# PBC.net
KiCad netlist of a schematic drawn in Altium Designer
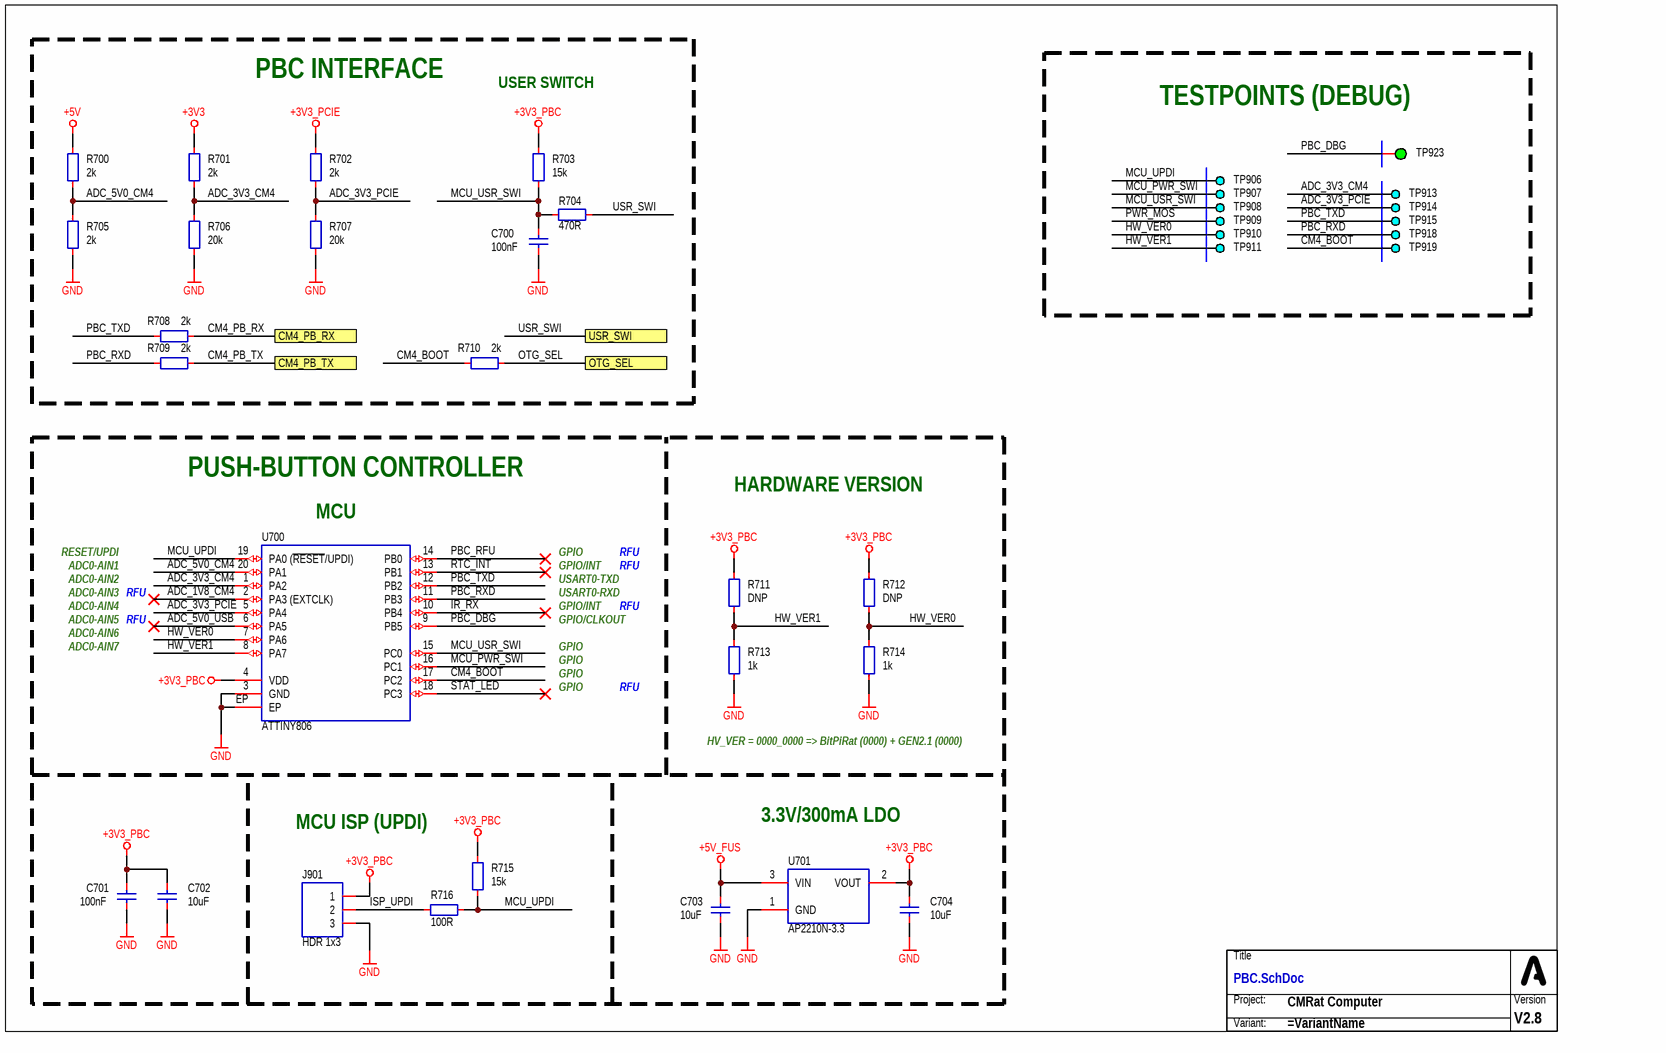
[diagram p0: PBC.SchDoc]

(export (version "E")
  (design (tool "Eeschema 10.0.6"))
  (components
    (comp (ref "C700")
      (value "100nF")
      (footprint "CAP_0603_R")
      (description "Capacitor; MLCC; 100nF; 10V X5R")
      (fields (field (name "MANUFACTURER") "YAGEO") (field (name "MPN") "CC0603KRX7R9BB104"))
      (libsource (lib "MirFol_db_local") (part "CAP"))
    )
    (comp (ref "C701")
      (value "100nF")
      (footprint "CAP_0603_R")
      (description "Capacitor; MLCC; 100nF; 10V X5R")
      (fields (field (name "MANUFACTURER") "YAGEO") (field (name "MPN") "CC0603KRX7R9BB104"))
      (libsource (lib "MirFol_db_local") (part "CAP"))
    )
    (comp (ref "C702")
      (value "10uF")
      (footprint "CAP_0603_R")
      (description "CAP SMD 10u/10V ±10% 10V X5R (0603)")
      (fields
        (field (name "MANUFACTURER") "Samsung Electro-Mechanics")
        (field (name "MPN") "CL10A106KP8NNNC")
      )
      (libsource (lib "MirFol_db_local") (part "CAP"))
    )
    (comp (ref "C703")
      (value "10uF")
      (footprint "CAP_0603_R")
      (description "CAP SMD 10u/10V ±10% 10V X5R (0603)")
      (fields
        (field (name "MANUFACTURER") "Samsung Electro-Mechanics")
        (field (name "MPN") "CL10A106KP8NNNC")
      )
      (libsource (lib "MirFol_db_local") (part "CAP"))
    )
    (comp (ref "C704")
      (value "10uF")
      (footprint "CAP_0603_R")
      (description "CAP SMD 10u/10V ±10% 10V X5R (0603)")
      (fields
        (field (name "MANUFACTURER") "Samsung Electro-Mechanics")
        (field (name "MPN") "CL10A106KP8NNNC")
      )
      (libsource (lib "MirFol_db_local") (part "CAP"))
    )
    (comp (ref "J901")
      (value "HDR 1x3")
      (footprint "CON_HDR_P254_1X03_STR")
      (description "CONN THT / HEADER / PITCH 2,54mm / VERTICAL / (3 PIN)")
      (fields
        (field (name "MANUFACTURER") "Ckmtw(Shenzhen Cankemeng)")
        (field (name "MPN") "B-2100S03P-A110")
      )
      (libsource (lib "MirFol_lib") (part "CON_1X03_COL"))
    )
    (comp (ref "R700")
      (value "2k")
      (footprint "RES_0603_R")
      (description "Resistor; Thick Film; 2k2; 1%; 100mW; 100PPM; 75V; Standard; SMD; 0603 (1608);")
      (fields (field (name "MANUFACTURER") "UNI-ROYAL(Uniroyal Elec)") (field (name "MPN") "0603WAF2001T5E"))
      (libsource (lib "") (part "RES_1"))
    )
    (comp (ref "R701")
      (value "2k")
      (footprint "RES_0603_R")
      (description "Resistor; Thick Film; 2k2; 1%; 100mW; 100PPM; 75V; Standard; SMD; 0603 (1608);")
      (fields (field (name "MANUFACTURER") "UNI-ROYAL(Uniroyal Elec)") (field (name "MPN") "0603WAF2001T5E"))
      (libsource (lib "") (part "RES_1"))
    )
    (comp (ref "R702")
      (value "2k")
      (footprint "RES_0603_R")
      (description "Resistor; Thick Film; 2k2; 1%; 100mW; 100PPM; 75V; Standard; SMD; 0603 (1608);")
      (fields (field (name "MANUFACTURER") "UNI-ROYAL(Uniroyal Elec)") (field (name "MPN") "0603WAF2001T5E"))
      (libsource (lib "") (part "RES_1"))
    )
    (comp (ref "R703")
      (value "15k")
      (footprint "RES_0603_R")
      (description "Resistor; Thick Film; 15k; 1%; 100mW; 100PPM; 75V; Standard; SMD; 0603 (1608);")
      (fields (field (name "MANUFACTURER") "UNI-ROYAL(Uniroyal Elec)") (field (name "MPN") "0603WAF1502T5E"))
      (libsource (lib "") (part "RES_2"))
    )
    (comp (ref "R704")
      (value "470R")
      (footprint "RES_0603_R")
      (description "Resistor; Thick Film; 470R; 1%; 100mW; 100PPM; 75V; Standard; SMD; 0603 (1608);")
      (fields (field (name "MANUFACTURER") "UNI-ROYAL(Uniroyal Elec)") (field (name "MPN") "0603WAF4700T5E"))
      (libsource (lib "") (part "RES_3"))
    )
    (comp (ref "R705")
      (value "2k")
      (footprint "RES_0603_R")
      (description "Resistor; Thick Film; 2k2; 1%; 100mW; 100PPM; 75V; Standard; SMD; 0603 (1608);")
      (fields (field (name "MANUFACTURER") "UNI-ROYAL(Uniroyal Elec)") (field (name "MPN") "0603WAF2001T5E"))
      (libsource (lib "") (part "RES_1"))
    )
    (comp (ref "R706")
      (value "20k")
      (footprint "RES_0603_R")
      (description "Resistor; Thick Film; 20k; SMD; 0603 (1608);")
      (fields (field (name "MANUFACTURER") "UNI-ROYAL(Uniroyal Elec)") (field (name "MPN") "0603WAF2002T5E"))
      (libsource (lib "") (part "RES_2"))
    )
    (comp (ref "R707")
      (value "20k")
      (footprint "RES_0603_R")
      (description "Resistor; Thick Film; 20k; SMD; 0603 (1608);")
      (fields (field (name "MANUFACTURER") "UNI-ROYAL(Uniroyal Elec)") (field (name "MPN") "0603WAF2002T5E"))
      (libsource (lib "") (part "RES_2"))
    )
    (comp (ref "R708")
      (value "2k")
      (footprint "RES_0603_R")
      (description "Resistor; Thick Film; 2k2; 1%; 100mW; 100PPM; 75V; Standard; SMD; 0603 (1608);")
      (fields (field (name "MANUFACTURER") "UNI-ROYAL(Uniroyal Elec)") (field (name "MPN") "0603WAF2001T5E"))
      (libsource (lib "MirFol_db_local") (part "RES"))
    )
    (comp (ref "R709")
      (value "2k")
      (footprint "RES_0603_R")
      (description "Resistor; Thick Film; 2k2; 1%; 100mW; 100PPM; 75V; Standard; SMD; 0603 (1608);")
      (fields (field (name "MANUFACTURER") "UNI-ROYAL(Uniroyal Elec)") (field (name "MPN") "0603WAF2001T5E"))
      (libsource (lib "MirFol_db_local") (part "RES"))
    )
    (comp (ref "R710")
      (value "2k")
      (footprint "RES_0603_R")
      (description "Resistor; Thick Film; 2k2; 1%; 100mW; 100PPM; 75V; Standard; SMD; 0603 (1608);")
      (fields (field (name "MANUFACTURER") "UNI-ROYAL(Uniroyal Elec)") (field (name "MPN") "0603WAF2001T5E"))
      (libsource (lib "") (part "RES_3"))
    )
    (comp (ref "R711") (value "DNP") (footprint "RES_0603_R") (libsource (lib "") (part "RES_2")))
    (comp (ref "R712") (value "DNP") (footprint "RES_0603_R") (libsource (lib "") (part "RES_2")))
    (comp (ref "R713")
      (value "1k")
      (footprint "RES_0603_R")
      (description "Resistor; Thick Film; 1k; 1%; 100mW; 100PPM; 75V; Standard; SMD; 0603 (1608);")
      (fields (field (name "MANUFACTURER") "UNI-ROYAL(Uniroyal Elec)") (field (name "MPN") "0603WAF1001T5E"))
      (libsource (lib "") (part "RES_2"))
    )
    (comp (ref "R714")
      (value "1k")
      (footprint "RES_0603_R")
      (description "Resistor; Thick Film; 1k; 1%; 100mW; 100PPM; 75V; Standard; SMD; 0603 (1608);")
      (fields (field (name "MANUFACTURER") "UNI-ROYAL(Uniroyal Elec)") (field (name "MPN") "0603WAF1001T5E"))
      (libsource (lib "") (part "RES_2"))
    )
    (comp (ref "R715")
      (value "15k")
      (footprint "RES_0603_R")
      (description "Resistor; Thick Film; 15k; 1%; 100mW; 100PPM; 75V; Standard; SMD; 0603 (1608);")
      (fields (field (name "MANUFACTURER") "UNI-ROYAL(Uniroyal Elec)") (field (name "MPN") "0603WAF1502T5E"))
      (libsource (lib "") (part "RES_2"))
    )
    (comp (ref "R716")
      (value "100R")
      (footprint "RES_0603_R")
      (description "Resistor; Thick Film; 100R; 1%; 100mW; 100PPM; 75V; Standard; SMD; 0603 (1608);")
      (fields (field (name "MANUFACTURER") "UNI-ROYAL(Uniroyal Elec)") (field (name "MPN") "0603WAF1000T5E"))
      (libsource (lib "MirFol_db_local") (part "RES"))
    )
    (comp (ref "TB700") (value "~") (libsource (lib "Symbols_NO_BOM") (part "SCH_TITLE_BLOCK_SIMPLE_NODATE")))
    (comp (ref "TP906")
      (value "DEBUG")
      (footprint "PCB_TP_DBG_50")
      (description "PCB Marking; Test Point (Debug);")
      (libsource (lib "MirFol_lib") (part "PCB_TP_DBG"))
    )
    (comp (ref "TP907")
      (value "DEBUG")
      (footprint "PCB_TP_DBG_50")
      (description "PCB Marking; Test Point (Debug);")
      (libsource (lib "MirFol_lib") (part "PCB_TP_DBG"))
    )
    (comp (ref "TP908")
      (value "DEBUG")
      (footprint "PCB_TP_DBG_50")
      (description "PCB Marking; Test Point (Debug);")
      (libsource (lib "MirFol_lib") (part "PCB_TP_DBG"))
    )
    (comp (ref "TP909")
      (value "DEBUG")
      (footprint "PCB_TP_DBG_50")
      (description "PCB Marking; Test Point (Debug);")
      (libsource (lib "MirFol_lib") (part "PCB_TP_DBG"))
    )
    (comp (ref "TP910")
      (value "DEBUG")
      (footprint "PCB_TP_DBG_50")
      (description "PCB Marking; Test Point (Debug);")
      (libsource (lib "MirFol_lib") (part "PCB_TP_DBG"))
    )
    (comp (ref "TP911")
      (value "DEBUG")
      (footprint "PCB_TP_DBG_50")
      (description "PCB Marking; Test Point (Debug);")
      (libsource (lib "MirFol_lib") (part "PCB_TP_DBG"))
    )
    (comp (ref "TP913")
      (value "DEBUG")
      (footprint "PCB_TP_DBG_50")
      (description "PCB Marking; Test Point (Debug);")
      (libsource (lib "MirFol_lib") (part "PCB_TP_DBG"))
    )
    (comp (ref "TP914")
      (value "DEBUG")
      (footprint "PCB_TP_DBG_50")
      (description "PCB Marking; Test Point (Debug);")
      (libsource (lib "MirFol_lib") (part "PCB_TP_DBG"))
    )
    (comp (ref "TP915")
      (value "DEBUG")
      (footprint "PCB_TP_DBG_50")
      (description "PCB Marking; Test Point (Debug);")
      (libsource (lib "MirFol_lib") (part "PCB_TP_DBG"))
    )
    (comp (ref "TP918")
      (value "DEBUG")
      (footprint "PCB_TP_DBG_50")
      (description "PCB Marking; Test Point (Debug);")
      (libsource (lib "MirFol_lib") (part "PCB_TP_DBG"))
    )
    (comp (ref "TP919")
      (value "DEBUG")
      (footprint "PCB_TP_DBG_50")
      (description "PCB Marking; Test Point (Debug);")
      (libsource (lib "MirFol_lib") (part "PCB_TP_DBG"))
    )
    (comp (ref "TP923")
      (value "ICT")
      (footprint "PCB_TP_ICT_100")
      (description "Test Point (ICT)")
      (libsource (lib "MirFol_lib") (part "PCB_TP_ICT"))
    )
    (comp (ref "U700")
      (value "ATTINY806")
      (footprint "ICC_QFN20_300X300X90_P40_EP_R")
      (description "IC; MCU; tinyAVR 8-bit MCU, 20MHz, 8kB flash, 512B RAM, USART, SPI, TWI, VQFN package")
      (fields
        (field (name "MANUFACTURER") "Microchip Technology (Atmel)")
        (field (name "MPN") "ATTINY806-MNR")
      )
      (libsource (lib "Pineberry_Lib") (part "ICC_MCP_ATTINY406_806_1606_VQFN20"))
    )
    (comp (ref "U701")
      (value "AP2210N-3.3")
      (footprint "PKG_SOT23-3L_SC59_P190_R")
      (fields (field (name "MANUFACTURER") "Diodes Incorporated") (field (name "MPN") "AP2210N-3.3TRG1"))
      (libsource (lib "Pineberry_Lib") (part "ICC_DIO_AP2210N-3.3TR"))
    )
  )
  (nets
    (net (code "1") (name "+3V3") (class "Default")
      (node (ref "R701") (pin "1") (pinfunction "1_1") (pintype "passive"))
    )
    (net (code "2") (name "+3V3_PBC") (class "Default")
      (node (ref "C701") (pin "2") (pintype "passive"))
      (node (ref "C702") (pin "2") (pintype "passive"))
      (node (ref "C704") (pin "2") (pintype "passive"))
      (node (ref "J901") (pin "1") (pinfunction "1_1") (pintype "passive"))
      (node (ref "R703") (pin "2") (pinfunction "2_2") (pintype "passive"))
      (node (ref "R711") (pin "2") (pinfunction "2_2") (pintype "passive"))
      (node (ref "R712") (pin "2") (pinfunction "2_2") (pintype "passive"))
      (node (ref "R715") (pin "2") (pinfunction "2_2") (pintype "passive"))
      (node (ref "U700") (pin "4") (pinfunction "VDD_4") (pintype "power_in"))
      (node (ref "U701") (pin "2") (pinfunction "VOUT_2") (pintype "power_in"))
    )
    (net (code "3") (name "+3V3_PCIE") (class "Default")
      (node (ref "R702") (pin "1") (pinfunction "1_1") (pintype "passive"))
    )
    (net (code "4") (name "+5V") (class "Default")
      (node (ref "R700") (pin "1") (pinfunction "1_1") (pintype "passive"))
    )
    (net (code "5") (name "+5V_FUS") (class "Default")
      (node (ref "C703") (pin "2") (pintype "passive"))
      (node (ref "U701") (pin "3") (pinfunction "VIN_3") (pintype "power_in"))
    )
    (net (code "6") (name "/ADC_1V8_CM4") (class "Default")
      (node (ref "U700") (pin "2") (pinfunction "PA3_(EXTCLK)_2") (pintype "bidirectional+no_connect"))
    )
    (net (code "7") (name "/ADC_3V3_CM4") (class "Default")
      (node (ref "R701") (pin "2") (pinfunction "2_2") (pintype "passive"))
      (node (ref "R706") (pin "2") (pinfunction "2_2") (pintype "passive"))
      (node (ref "TP913") (pin "1") (pinfunction "1_1") (pintype "passive"))
      (node (ref "U700") (pin "1") (pinfunction "PA2_1") (pintype "bidirectional"))
    )
    (net (code "8") (name "/ADC_3V3_PCIE") (class "Default")
      (node (ref "R702") (pin "2") (pinfunction "2_2") (pintype "passive"))
      (node (ref "R707") (pin "2") (pinfunction "2_2") (pintype "passive"))
      (node (ref "TP914") (pin "1") (pinfunction "1_1") (pintype "passive"))
      (node (ref "U700") (pin "5") (pinfunction "PA4_5") (pintype "bidirectional"))
    )
    (net (code "9") (name "/ADC_5V0_CM4") (class "Default")
      (node (ref "R700") (pin "2") (pinfunction "2_2") (pintype "passive"))
      (node (ref "R705") (pin "1") (pinfunction "1_1") (pintype "passive"))
      (node (ref "U700") (pin "20") (pinfunction "PA1_20") (pintype "bidirectional"))
    )
    (net (code "10") (name "/ADC_5V0_USB") (class "Default")
      (node (ref "U700") (pin "6") (pinfunction "PA5_6") (pintype "bidirectional+no_connect"))
    )
    (net (code "11") (name "/CM4_BOOT") (class "Default")
      (node (ref "R710") (pin "2") (pinfunction "2_2") (pintype "passive"))
      (node (ref "TP919") (pin "1") (pinfunction "1_1") (pintype "passive"))
      (node (ref "U700") (pin "17") (pinfunction "PC2_17") (pintype "bidirectional"))
    )
    (net (code "12") (name "/CM4_PB_RX") (class "Default")
      (node (ref "R708") (pin "2") (pinfunction "2_2") (pintype "passive"))
    )
    (net (code "13") (name "/CM4_PB_TX") (class "Default")
      (node (ref "R709") (pin "2") (pinfunction "2_2") (pintype "passive"))
    )
    (net (code "14") (name "/HW_VER0") (class "Default")
      (node (ref "R712") (pin "1") (pinfunction "1_1") (pintype "passive"))
      (node (ref "R714") (pin "2") (pinfunction "2_2") (pintype "passive"))
      (node (ref "TP910") (pin "1") (pinfunction "1_1") (pintype "passive"))
      (node (ref "U700") (pin "7") (pinfunction "PA6_7") (pintype "bidirectional"))
    )
    (net (code "15") (name "/HW_VER1") (class "Default")
      (node (ref "R711") (pin "1") (pinfunction "1_1") (pintype "passive"))
      (node (ref "R713") (pin "2") (pinfunction "2_2") (pintype "passive"))
      (node (ref "TP911") (pin "1") (pinfunction "1_1") (pintype "passive"))
      (node (ref "U700") (pin "8") (pinfunction "PA7_8") (pintype "bidirectional"))
    )
    (net (code "16") (name "/IR_RX") (class "Default")
      (node (ref "U700") (pin "10") (pinfunction "PB4_10") (pintype "bidirectional+no_connect"))
    )
    (net (code "17") (name "/ISP_UPDI") (class "Default")
      (node (ref "J901") (pin "2") (pinfunction "2_2") (pintype "passive"))
      (node (ref "R716") (pin "1") (pinfunction "1_1") (pintype "passive"))
    )
    (net (code "18") (name "/MCU_PWR_SWI") (class "Default")
      (node (ref "TP907") (pin "1") (pinfunction "1_1") (pintype "passive"))
      (node (ref "U700") (pin "16") (pinfunction "PC1_16") (pintype "bidirectional"))
    )
    (net (code "19") (name "/MCU_UPDI") (class "Default")
      (node (ref "R715") (pin "1") (pinfunction "1_1") (pintype "passive"))
      (node (ref "R716") (pin "2") (pinfunction "2_2") (pintype "passive"))
      (node (ref "TP906") (pin "1") (pinfunction "1_1") (pintype "passive"))
      (node (ref "U700") (pin "19") (pinfunction "PA0_(~{RESET}/UPDI)_19") (pintype "bidirectional"))
    )
    (net (code "20") (name "/MCU_USR_SWI") (class "Default")
      (node (ref "C700") (pin "2") (pintype "passive"))
      (node (ref "R703") (pin "1") (pinfunction "1_1") (pintype "passive"))
      (node (ref "R704") (pin "2") (pinfunction "2_2") (pintype "passive"))
      (node (ref "TP908") (pin "1") (pinfunction "1_1") (pintype "passive"))
      (node (ref "U700") (pin "15") (pinfunction "PC0_15") (pintype "bidirectional"))
    )
    (net (code "21") (name "/OTG_SEL") (class "Default")
      (node (ref "R710") (pin "1") (pinfunction "1_1") (pintype "passive"))
    )
    (net (code "22") (name "/PBC_DBG") (class "Default")
      (node (ref "TP923") (pin "1") (pinfunction "1_1") (pintype "passive"))
      (node (ref "U700") (pin "9") (pinfunction "PB5_9") (pintype "bidirectional"))
    )
    (net (code "23") (name "/PBC_RFU") (class "Default")
      (node (ref "U700") (pin "14") (pinfunction "PB0_14") (pintype "bidirectional+no_connect"))
    )
    (net (code "24") (name "/PBC_RXD") (class "Default")
      (node (ref "R709") (pin "1") (pinfunction "1_1") (pintype "passive"))
      (node (ref "TP918") (pin "1") (pinfunction "1_1") (pintype "passive"))
      (node (ref "U700") (pin "11") (pinfunction "PB3_11") (pintype "bidirectional"))
    )
    (net (code "25") (name "/PBC_TXD") (class "Default")
      (node (ref "R708") (pin "1") (pinfunction "1_1") (pintype "passive"))
      (node (ref "TP915") (pin "1") (pinfunction "1_1") (pintype "passive"))
      (node (ref "U700") (pin "12") (pinfunction "PB2_12") (pintype "bidirectional"))
    )
    (net (code "26") (name "/PWR_MOS") (class "Default")
      (node (ref "TP909") (pin "1") (pinfunction "1_1") (pintype "passive"))
    )
    (net (code "27") (name "/RTC_INT") (class "Default")
      (node (ref "U700") (pin "13") (pinfunction "PB1_13") (pintype "bidirectional+no_connect"))
    )
    (net (code "28") (name "/STAT_LED") (class "Default")
      (node (ref "U700") (pin "18") (pinfunction "PC3_18") (pintype "bidirectional+no_connect"))
    )
    (net (code "29") (name "/USR_SWI") (class "Default")
      (node (ref "R704") (pin "1") (pinfunction "1_1") (pintype "passive"))
    )
    (net (code "30") (name "GND") (class "Default")
      (node (ref "C700") (pin "1") (pintype "passive"))
      (node (ref "C701") (pin "1") (pintype "passive"))
      (node (ref "C702") (pin "1") (pintype "passive"))
      (node (ref "C703") (pin "1") (pintype "passive"))
      (node (ref "C704") (pin "1") (pintype "passive"))
      (node (ref "J901") (pin "3") (pinfunction "3_3") (pintype "passive"))
      (node (ref "R705") (pin "2") (pinfunction "2_2") (pintype "passive"))
      (node (ref "R706") (pin "1") (pinfunction "1_1") (pintype "passive"))
      (node (ref "R707") (pin "1") (pinfunction "1_1") (pintype "passive"))
      (node (ref "R713") (pin "1") (pinfunction "1_1") (pintype "passive"))
      (node (ref "R714") (pin "1") (pinfunction "1_1") (pintype "passive"))
      (node (ref "U700") (pin "3") (pinfunction "GND_3") (pintype "power_in"))
      (node (ref "U700") (pin "EP") (pinfunction "EP_EP") (pintype "power_in"))
      (node (ref "U701") (pin "1") (pinfunction "GND_1") (pintype "power_in"))
    )
  )
)
